# RN2483_2903_1ANT_RevA.net
KiCad netlist of a schematic drawn in EAGLE
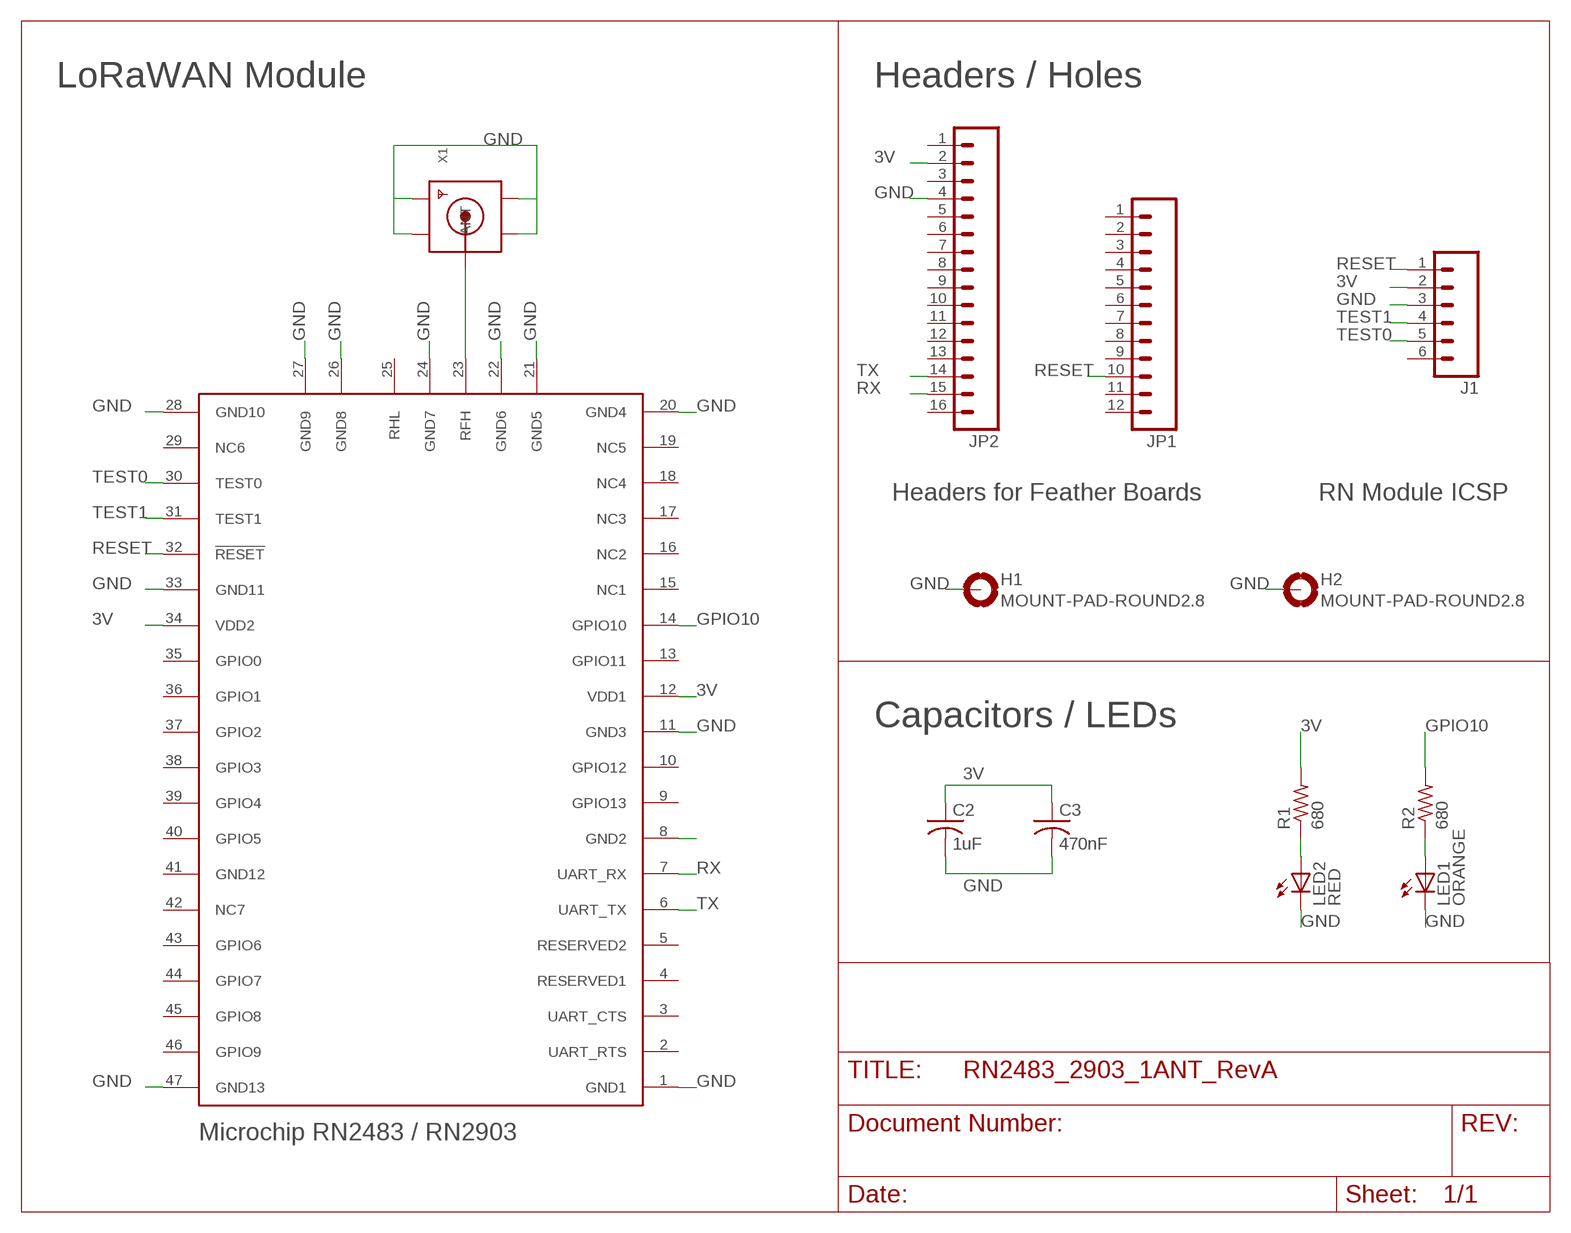
[diagram p0: schematic, sheet 1]

(export (version "E")
  (design (tool "Eeschema 10.0.6"))
  (components
    (comp (ref "C2")
      (value "1uF")
      (footprint "eagle-import:C0603")
      (libsource (lib "eagle-import") (part "C-USC0603"))
    )
    (comp (ref "C3")
      (value "470nF")
      (footprint "eagle-import:C0603")
      (libsource (lib "eagle-import") (part "C-USC0603"))
    )
    (comp (ref "H1")
      (value "MOUNT-PAD-ROUND2.8")
      (footprint "eagle-import:2,8-PAD")
      (libsource (lib "eagle-import") (part "MOUNT-PAD-ROUND2.8"))
    )
    (comp (ref "H2")
      (value "MOUNT-PAD-ROUND2.8")
      (footprint "eagle-import:2,8-PAD")
      (libsource (lib "eagle-import") (part "MOUNT-PAD-ROUND2.8"))
    )
    (comp (ref "J1")
      (value "M06SILK_FEMALE_PTH")
      (footprint "eagle-import:1X06")
      (libsource (lib "eagle-import") (part "M06SILK_FEMALE_PTH"))
    )
    (comp (ref "JP1")
      (value "M12NO_SILK")
      (footprint "eagle-import:1X12_NO_SILK")
      (libsource (lib "eagle-import") (part "M12NO_SILK"))
    )
    (comp (ref "JP2")
      (value "M161X16_NO_SILK")
      (footprint "eagle-import:1X16_NO_SILK")
      (libsource (lib "eagle-import") (part "M161X16_NO_SILK"))
    )
    (comp (ref "LED1")
      (value "ORANGE")
      (footprint "eagle-import:CHIPLED_0805")
      (libsource (lib "eagle-import") (part "LEDCHIPLED_0805"))
    )
    (comp (ref "LED2")
      (value "RED")
      (footprint "eagle-import:CHIPLED_0805")
      (libsource (lib "eagle-import") (part "LEDCHIPLED_0805"))
    )
    (comp (ref "R1")
      (value "680")
      (footprint "eagle-import:R0603")
      (libsource (lib "eagle-import") (part "R-US_R0603"))
    )
    (comp (ref "R2")
      (value "680")
      (footprint "eagle-import:R0603")
      (libsource (lib "eagle-import") (part "R-US_R0603"))
    )
    (comp (ref "U$2")
      (value "RN2483/2903")
      (footprint "eagle-import:RN2483_2903")
      (libsource (lib "eagle-import") (part "RN2483/2903"))
    )
    (comp (ref "X1")
      (value "SMACONNECTOR_EDGE")
      (footprint "eagle-import:SMA_EDGELAUNCH")
      (libsource (lib "eagle-import") (part "SMACONNECTOR_EDGE"))
    )
  )
  (nets
    (net (code "1") (name "/3V") (class "Default")
      (node (ref "C2") (pin "1") (pinfunction "1_1") (pintype "passive"))
      (node (ref "C3") (pin "1") (pinfunction "1_1") (pintype "passive"))
      (node (ref "J1") (pin "2") (pinfunction "2_2") (pintype "passive"))
      (node (ref "JP2") (pin "2") (pinfunction "2_2") (pintype "passive"))
      (node (ref "R1") (pin "2") (pinfunction "2_2") (pintype "passive"))
      (node (ref "U$2") (pin "12") (pinfunction "VDD1_12") (pintype "bidirectional"))
      (node (ref "U$2") (pin "34") (pinfunction "VDD2_34") (pintype "bidirectional"))
    )
    (net (code "2") (name "/GND") (class "Default")
      (node (ref "C2") (pin "2") (pinfunction "2_2") (pintype "passive"))
      (node (ref "C3") (pin "2") (pinfunction "2_2") (pintype "passive"))
      (node (ref "H1") (pin "B2,8") (pinfunction "MOUNT_B2,8") (pintype "passive"))
      (node (ref "H2") (pin "B2,8") (pinfunction "MOUNT_B2,8") (pintype "passive"))
      (node (ref "J1") (pin "3") (pinfunction "3_3") (pintype "passive"))
      (node (ref "JP2") (pin "4") (pinfunction "4_4") (pintype "passive"))
      (node (ref "LED1") (pin "C") (pinfunction "C_C") (pintype "passive"))
      (node (ref "LED2") (pin "C") (pinfunction "C_C") (pintype "passive"))
      (node (ref "U$2") (pin "1") (pinfunction "GND1_1") (pintype "bidirectional"))
      (node (ref "U$2") (pin "11") (pinfunction "GND3_11") (pintype "bidirectional"))
      (node (ref "U$2") (pin "20") (pinfunction "GND4_20") (pintype "bidirectional"))
      (node (ref "U$2") (pin "21") (pinfunction "GND5_21") (pintype "bidirectional"))
      (node (ref "U$2") (pin "22") (pinfunction "GND6_22") (pintype "bidirectional"))
      (node (ref "U$2") (pin "24") (pinfunction "GND7_24") (pintype "bidirectional"))
      (node (ref "U$2") (pin "26") (pinfunction "GND8_26") (pintype "bidirectional"))
      (node (ref "U$2") (pin "27") (pinfunction "GND9_27") (pintype "bidirectional"))
      (node (ref "U$2") (pin "28") (pinfunction "GND10_28") (pintype "bidirectional"))
      (node (ref "U$2") (pin "33") (pinfunction "GND11_33") (pintype "bidirectional"))
      (node (ref "U$2") (pin "47") (pinfunction "GND13_47") (pintype "bidirectional"))
      (node (ref "X1") (pin "GND@1") (pinfunction "GND4_GND@1") (pintype "power_in"))
      (node (ref "X1") (pin "GND@2") (pinfunction "GND3_GND@2") (pintype "power_in"))
      (node (ref "X1") (pin "GND@3") (pinfunction "GND2_GND@3") (pintype "power_in"))
      (node (ref "X1") (pin "GND@4") (pinfunction "GND1_GND@4") (pintype "power_in"))
    )
    (net (code "3") (name "/GPIO10") (class "Default")
      (node (ref "R2") (pin "2") (pinfunction "2_2") (pintype "passive"))
      (node (ref "U$2") (pin "14") (pinfunction "GPIO10_14") (pintype "bidirectional"))
    )
    (net (code "4") (name "/RESET") (class "Default")
      (node (ref "J1") (pin "1") (pinfunction "1_1") (pintype "passive"))
      (node (ref "JP1") (pin "10") (pinfunction "10_10") (pintype "passive"))
      (node (ref "U$2") (pin "32") (pinfunction "~{RESET}_32") (pintype "bidirectional"))
    )
    (net (code "5") (name "/RX") (class "Default")
      (node (ref "JP2") (pin "15") (pinfunction "15_15") (pintype "passive"))
      (node (ref "U$2") (pin "7") (pinfunction "UART_RX_7") (pintype "bidirectional"))
    )
    (net (code "6") (name "/TEST0") (class "Default")
      (node (ref "J1") (pin "5") (pinfunction "5_5") (pintype "passive"))
      (node (ref "U$2") (pin "30") (pinfunction "TEST0_30") (pintype "bidirectional"))
    )
    (net (code "7") (name "/TEST1") (class "Default")
      (node (ref "J1") (pin "4") (pinfunction "4_4") (pintype "passive"))
      (node (ref "U$2") (pin "31") (pinfunction "TEST1_31") (pintype "bidirectional"))
    )
    (net (code "8") (name "/TX") (class "Default")
      (node (ref "JP2") (pin "14") (pinfunction "14_14") (pintype "passive"))
      (node (ref "U$2") (pin "6") (pinfunction "UART_TX_6") (pintype "bidirectional"))
    )
    (net (code "9") (name "Net-(LED1-PadA)") (class "Default")
      (node (ref "LED1") (pin "A") (pinfunction "A_A") (pintype "passive"))
      (node (ref "R2") (pin "1") (pinfunction "1_1") (pintype "passive"))
    )
    (net (code "10") (name "Net-(LED2-PadA)") (class "Default")
      (node (ref "LED2") (pin "A") (pinfunction "A_A") (pintype "passive"))
      (node (ref "R1") (pin "1") (pinfunction "1_1") (pintype "passive"))
    )
    (net (code "11") (name "Net-(U$2-RFH)") (class "Default")
      (node (ref "U$2") (pin "23") (pinfunction "RFH_23") (pintype "bidirectional"))
      (node (ref "X1") (pin "P") (pinfunction "ANT_P") (pintype "bidirectional"))
    )
    (net (code "12") (name "unconnected-(J1-Pad6)") (class "Default")
      (node (ref "J1") (pin "6") (pinfunction "6_6") (pintype "passive"))
    )
    (net (code "13") (name "unconnected-(JP1-Pad1)") (class "Default")
      (node (ref "JP1") (pin "1") (pinfunction "1_1") (pintype "passive"))
    )
    (net (code "14") (name "unconnected-(JP1-Pad2)") (class "Default")
      (node (ref "JP1") (pin "2") (pinfunction "2_2") (pintype "passive"))
    )
    (net (code "15") (name "unconnected-(JP1-Pad3)") (class "Default")
      (node (ref "JP1") (pin "3") (pinfunction "3_3") (pintype "passive"))
    )
    (net (code "16") (name "unconnected-(JP1-Pad4)") (class "Default")
      (node (ref "JP1") (pin "4") (pinfunction "4_4") (pintype "passive"))
    )
    (net (code "17") (name "unconnected-(JP1-Pad5)") (class "Default")
      (node (ref "JP1") (pin "5") (pinfunction "5_5") (pintype "passive"))
    )
    (net (code "18") (name "unconnected-(JP1-Pad6)") (class "Default")
      (node (ref "JP1") (pin "6") (pinfunction "6_6") (pintype "passive"))
    )
    (net (code "19") (name "unconnected-(JP1-Pad7)") (class "Default")
      (node (ref "JP1") (pin "7") (pinfunction "7_7") (pintype "passive"))
    )
    (net (code "20") (name "unconnected-(JP1-Pad8)") (class "Default")
      (node (ref "JP1") (pin "8") (pinfunction "8_8") (pintype "passive"))
    )
    (net (code "21") (name "unconnected-(JP1-Pad9)") (class "Default")
      (node (ref "JP1") (pin "9") (pinfunction "9_9") (pintype "passive"))
    )
    (net (code "22") (name "unconnected-(JP1-Pad11)") (class "Default")
      (node (ref "JP1") (pin "11") (pinfunction "11_11") (pintype "passive"))
    )
    (net (code "23") (name "unconnected-(JP1-Pad12)") (class "Default")
      (node (ref "JP1") (pin "12") (pinfunction "12_12") (pintype "passive"))
    )
    (net (code "24") (name "unconnected-(JP2-Pad1)") (class "Default")
      (node (ref "JP2") (pin "1") (pinfunction "1_1") (pintype "passive"))
    )
    (net (code "25") (name "unconnected-(JP2-Pad3)") (class "Default")
      (node (ref "JP2") (pin "3") (pinfunction "3_3") (pintype "passive"))
    )
    (net (code "26") (name "unconnected-(JP2-Pad5)") (class "Default")
      (node (ref "JP2") (pin "5") (pinfunction "5_5") (pintype "passive"))
    )
    (net (code "27") (name "unconnected-(JP2-Pad6)") (class "Default")
      (node (ref "JP2") (pin "6") (pinfunction "6_6") (pintype "passive"))
    )
    (net (code "28") (name "unconnected-(JP2-Pad7)") (class "Default")
      (node (ref "JP2") (pin "7") (pinfunction "7_7") (pintype "passive"))
    )
    (net (code "29") (name "unconnected-(JP2-Pad8)") (class "Default")
      (node (ref "JP2") (pin "8") (pinfunction "8_8") (pintype "passive"))
    )
    (net (code "30") (name "unconnected-(JP2-Pad9)") (class "Default")
      (node (ref "JP2") (pin "9") (pinfunction "9_9") (pintype "passive"))
    )
    (net (code "31") (name "unconnected-(JP2-Pad10)") (class "Default")
      (node (ref "JP2") (pin "10") (pinfunction "10_10") (pintype "passive"))
    )
    (net (code "32") (name "unconnected-(JP2-Pad11)") (class "Default")
      (node (ref "JP2") (pin "11") (pinfunction "11_11") (pintype "passive"))
    )
    (net (code "33") (name "unconnected-(JP2-Pad12)") (class "Default")
      (node (ref "JP2") (pin "12") (pinfunction "12_12") (pintype "passive"))
    )
    (net (code "34") (name "unconnected-(JP2-Pad13)") (class "Default")
      (node (ref "JP2") (pin "13") (pinfunction "13_13") (pintype "passive"))
    )
    (net (code "35") (name "unconnected-(JP2-Pad16)") (class "Default")
      (node (ref "JP2") (pin "16") (pinfunction "16_16") (pintype "passive"))
    )
    (net (code "36") (name "unconnected-(U$2-GND2-Pad8)") (class "Default")
      (node (ref "U$2") (pin "8") (pinfunction "GND2_8") (pintype "bidirectional"))
    )
    (net (code "37") (name "unconnected-(U$2-GND12-Pad41)") (class "Default")
      (node (ref "U$2") (pin "41") (pinfunction "GND12_41") (pintype "bidirectional"))
    )
    (net (code "38") (name "unconnected-(U$2-GPIO0-Pad35)") (class "Default")
      (node (ref "U$2") (pin "35") (pinfunction "GPIO0_35") (pintype "bidirectional"))
    )
    (net (code "39") (name "unconnected-(U$2-GPIO1-Pad36)") (class "Default")
      (node (ref "U$2") (pin "36") (pinfunction "GPIO1_36") (pintype "bidirectional"))
    )
    (net (code "40") (name "unconnected-(U$2-GPIO2-Pad37)") (class "Default")
      (node (ref "U$2") (pin "37") (pinfunction "GPIO2_37") (pintype "bidirectional"))
    )
    (net (code "41") (name "unconnected-(U$2-GPIO3-Pad38)") (class "Default")
      (node (ref "U$2") (pin "38") (pinfunction "GPIO3_38") (pintype "bidirectional"))
    )
    (net (code "42") (name "unconnected-(U$2-GPIO4-Pad39)") (class "Default")
      (node (ref "U$2") (pin "39") (pinfunction "GPIO4_39") (pintype "bidirectional"))
    )
    (net (code "43") (name "unconnected-(U$2-GPIO5-Pad40)") (class "Default")
      (node (ref "U$2") (pin "40") (pinfunction "GPIO5_40") (pintype "bidirectional"))
    )
    (net (code "44") (name "unconnected-(U$2-GPIO6-Pad43)") (class "Default")
      (node (ref "U$2") (pin "43") (pinfunction "GPIO6_43") (pintype "bidirectional"))
    )
    (net (code "45") (name "unconnected-(U$2-GPIO7-Pad44)") (class "Default")
      (node (ref "U$2") (pin "44") (pinfunction "GPIO7_44") (pintype "bidirectional"))
    )
    (net (code "46") (name "unconnected-(U$2-GPIO8-Pad45)") (class "Default")
      (node (ref "U$2") (pin "45") (pinfunction "GPIO8_45") (pintype "bidirectional"))
    )
    (net (code "47") (name "unconnected-(U$2-GPIO9-Pad46)") (class "Default")
      (node (ref "U$2") (pin "46") (pinfunction "GPIO9_46") (pintype "bidirectional"))
    )
    (net (code "48") (name "unconnected-(U$2-GPIO11-Pad13)") (class "Default")
      (node (ref "U$2") (pin "13") (pinfunction "GPIO11_13") (pintype "bidirectional"))
    )
    (net (code "49") (name "unconnected-(U$2-GPIO12-Pad10)") (class "Default")
      (node (ref "U$2") (pin "10") (pinfunction "GPIO12_10") (pintype "bidirectional"))
    )
    (net (code "50") (name "unconnected-(U$2-GPIO13-Pad9)") (class "Default")
      (node (ref "U$2") (pin "9") (pinfunction "GPIO13_9") (pintype "bidirectional"))
    )
    (net (code "51") (name "unconnected-(U$2-NC1-Pad15)") (class "Default")
      (node (ref "U$2") (pin "15") (pinfunction "NC1_15") (pintype "bidirectional"))
    )
    (net (code "52") (name "unconnected-(U$2-NC2-Pad16)") (class "Default")
      (node (ref "U$2") (pin "16") (pinfunction "NC2_16") (pintype "bidirectional"))
    )
    (net (code "53") (name "unconnected-(U$2-NC3-Pad17)") (class "Default")
      (node (ref "U$2") (pin "17") (pinfunction "NC3_17") (pintype "bidirectional"))
    )
    (net (code "54") (name "unconnected-(U$2-NC4-Pad18)") (class "Default")
      (node (ref "U$2") (pin "18") (pinfunction "NC4_18") (pintype "bidirectional"))
    )
    (net (code "55") (name "unconnected-(U$2-NC5-Pad19)") (class "Default")
      (node (ref "U$2") (pin "19") (pinfunction "NC5_19") (pintype "bidirectional"))
    )
    (net (code "56") (name "unconnected-(U$2-NC6-Pad29)") (class "Default")
      (node (ref "U$2") (pin "29") (pinfunction "NC6_29") (pintype "bidirectional"))
    )
    (net (code "57") (name "unconnected-(U$2-NC7-Pad42)") (class "Default")
      (node (ref "U$2") (pin "42") (pinfunction "NC7_42") (pintype "bidirectional"))
    )
    (net (code "58") (name "unconnected-(U$2-RESERVED1-Pad4)") (class "Default")
      (node (ref "U$2") (pin "4") (pinfunction "RESERVED1_4") (pintype "bidirectional"))
    )
    (net (code "59") (name "unconnected-(U$2-RESERVED2-Pad5)") (class "Default")
      (node (ref "U$2") (pin "5") (pinfunction "RESERVED2_5") (pintype "bidirectional"))
    )
    (net (code "60") (name "unconnected-(U$2-RHL-Pad25)") (class "Default")
      (node (ref "U$2") (pin "25") (pinfunction "RHL_25") (pintype "bidirectional"))
    )
    (net (code "61") (name "unconnected-(U$2-UART_CTS-Pad3)") (class "Default")
      (node (ref "U$2") (pin "3") (pinfunction "UART_CTS_3") (pintype "bidirectional"))
    )
    (net (code "62") (name "unconnected-(U$2-UART_RTS-Pad2)") (class "Default")
      (node (ref "U$2") (pin "2") (pinfunction "UART_RTS_2") (pintype "bidirectional"))
    )
  )
)
